# Peripherals.net
KiCad netlist of a schematic drawn in Altium Designer
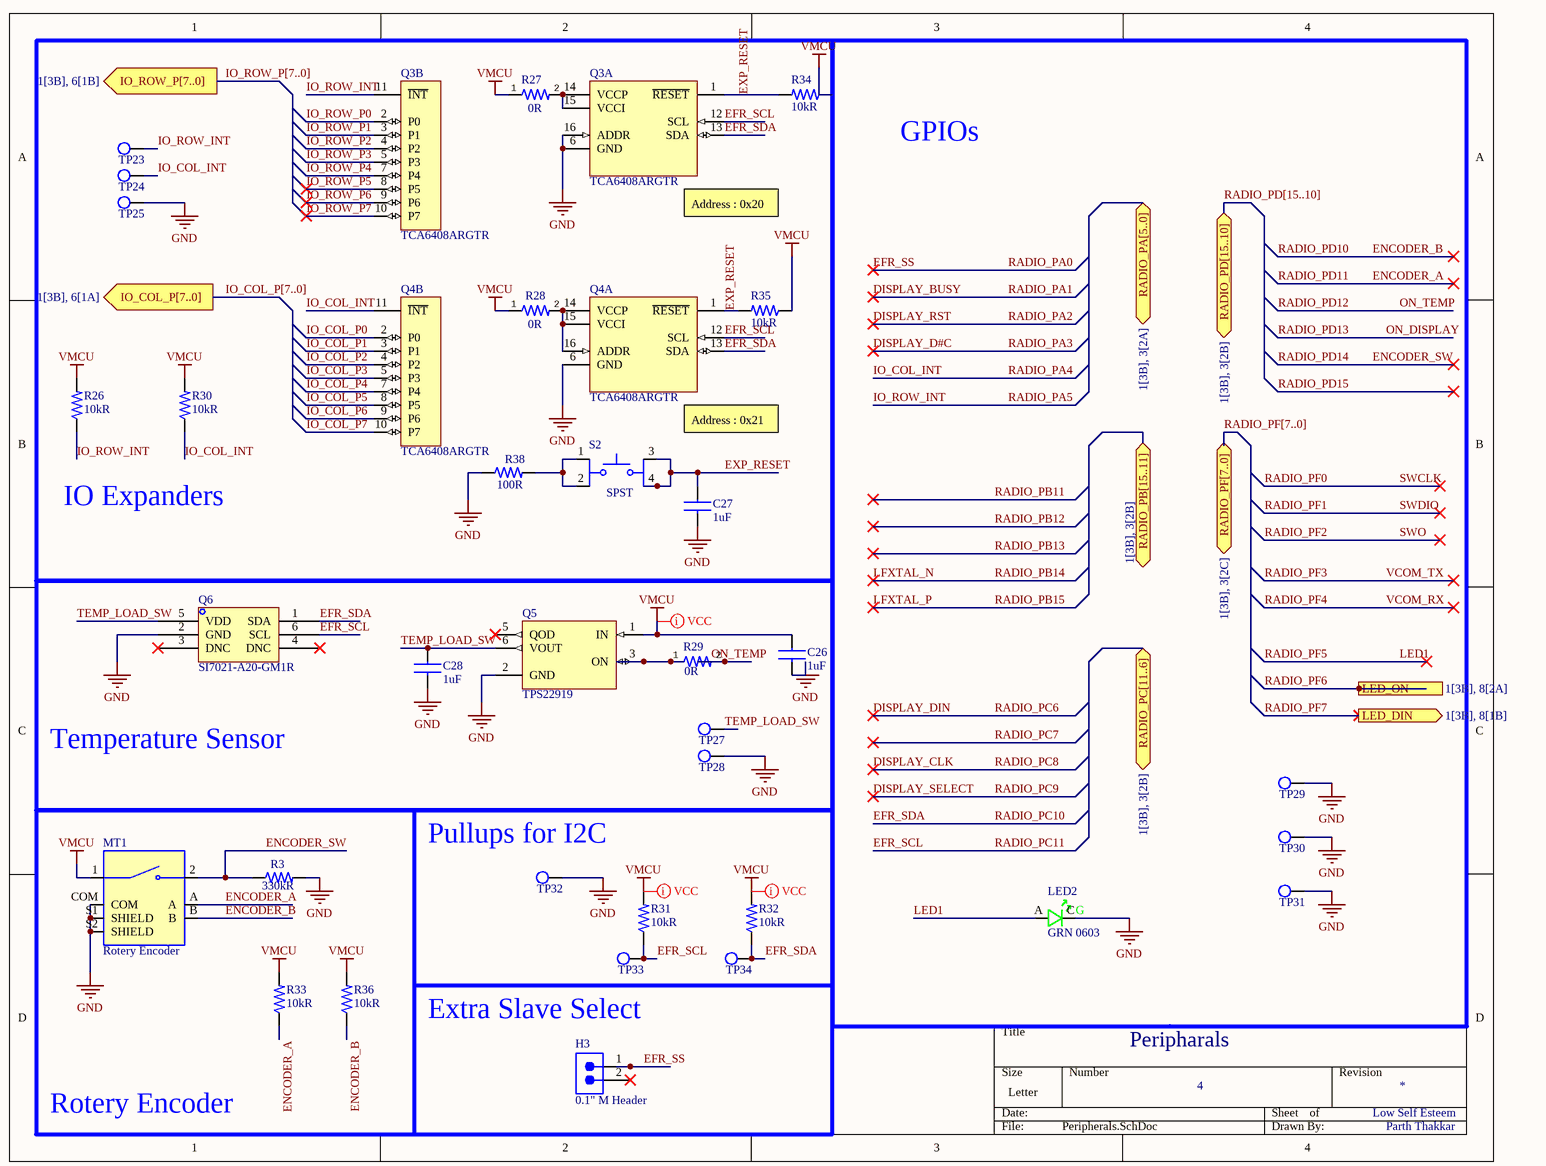
[diagram p0: Peripherals.SchDoc]

(export (version "E")
  (design (tool "Eeschema 10.0.6"))
  (components
    (comp (ref "C26")
      (value "1uF")
      (footprint "Capacitor 0603")
      (fields
        (field (name "MANUFACTURER") "Murata")
        (field (name "MANUFACTURER PART NUMBER") "GRM188R61A105KA61D")
        (field (name "Comment") "CAP 1uF 10V 0603")
      )
      (libsource (lib "Keyboard_parts") (part "CAP 1uF 10V 0603"))
    )
    (comp (ref "C27")
      (value "1uF")
      (footprint "Capacitor 0603")
      (fields
        (field (name "MANUFACTURER") "Murata")
        (field (name "MANUFACTURER PART NUMBER") "GRM188R61A105KA61D")
        (field (name "Comment") "CAP 1uF 10V 0603")
      )
      (libsource (lib "Keyboard_parts") (part "CAP 1uF 10V 0603"))
    )
    (comp (ref "C28")
      (value "1uF")
      (footprint "CAPACITOR 0805")
      (description "Multilayer Ceramic Capacitor, 1 uF, 10 V, ± 20%, X5R, 0201 [0603 Metric]")
      (fields
        (field (name "MANUFACTURER") "Murata")
        (field (name "MANUFACTURER PART NUMBER") "GRM033R61A105ME15D")
      )
      (libsource (lib "Keyboard_parts") (part "CAP 47uF 10V 0805"))
    )
    (comp (ref "H3")
      (value "0.1\" M Header")
      (footprint "2-PIN_MALE_HEADER_01-IN")
      (description "CONN HEADER VERT 2POS 2.54MM")
      (fields
        (field (name "MANUFACTURER") "Sullins")
        (field (name "MANUFACTURER PART NUMBER") "PRPC002SAAN-RC")
      )
      (libsource (lib "InsaneIntegratedLib") (part "PRPC002SAAN-RC"))
    )
    (comp (ref "LED2")
      (value "GRN 0603")
      (footprint "LED 0603")
      (description "LED, 0603, GREEN, 430MCD, 520NM")
      (fields
        (field (name "MANUFACTURER") "Wurth Electronics")
        (field (name "MANUFACTURER PART NUMBER") "150060GS75000")
      )
      (libsource (lib "InsaneIntegratedLib") (part "LED Green 0603"))
    )
    (comp (ref "MT1")
      (value "Rotery Encoder")
      (footprint "Rotery Encoder")
      (description "Rotary Position Encoder, Single, 2 Channels")
      (fields (field (name "MP") "PEC11R-4215F-S0024") (field (name "MANUFACTURER") "Bourns"))
      (libsource (lib "InsaneIntegratedLib") (part "Rotery Encoder"))
    )
    (comp (ref "Q3")
      (value "TCA6408ARGTR")
      (footprint "TCA6408ARGTR - IO Expander")
      (description "Parallel I/O Port, 8-Bit, 8 I/O, CMOS, PQCC16")
      (fields (field (name "MANUFACTURER") "Texas Instruments"))
      (libsource (lib "Keyboard_parts") (part "TCA6408ARGTR"))
    )
    (comp (ref "Q4")
      (value "TCA6408ARGTR")
      (footprint "TCA6408ARGTR - IO Expander")
      (description "Parallel I/O Port, 8-Bit, 8 I/O, CMOS, PQCC16")
      (fields (field (name "MANUFACTURER") "Texas Instruments"))
      (libsource (lib "Keyboard_parts") (part "TCA6408ARGTR"))
    )
    (comp (ref "Q5")
      (value "TPS22919")
      (footprint "TPS22919DCKR - Load SW")
      (description "Buffer/Inverter Based Peripheral Driver, 3A, PDSO6")
      (fields
        (field (name "MANUFACTURER") "Texas Instruments")
        (field (name "MANUFACTURER PART NUMBER") "TPS22919DCKT")
      )
      (libsource (lib "Keyboard_parts") (part "TPS22919"))
    )
    (comp (ref "Q6")
      (value "SI7021-A20-GM1R")
      (footprint "Si7021-A20 - Temp")
      (description "Serial Switch/Digital Sensor, 14 Bit(s), 0.40Cel, Square, Surface Mount")
      (fields (field (name "MANUFACTURER") "Silicon Labs"))
      (libsource (lib "Keyboard_parts") (part "SI7021-A20-GM1R"))
    )
    (comp (ref "R3")
      (value "330kR")
      (footprint "Resistor 0603")
      (fields
        (field (name "MANUFACTURER") "Yageo")
        (field (name "MANUFACTURER PART NUMBER") "RC0603JR-07330KL")
        (field (name "TOLERANCE") "5%")
      )
      (libsource (lib "Keyboard_parts") (part "RES 330K 0603"))
    )
    (comp (ref "R26")
      (value "10kR")
      (footprint "Resistor 0603")
      (fields
        (field (name "MANUFACTURER") "Yageo")
        (field (name "MANUFACTURER PART NUMBER") "RC0603FR-0710KL")
        (field (name "TOLERANCE") "1%")
      )
      (libsource (lib "Keyboard_parts") (part "RES 10K 0603"))
    )
    (comp (ref "R27")
      (value "0R")
      (footprint "Resistor 0402")
      (description "Metal Glaze/thick Film, 0.0625W, 0ohm, Surface Mount, 0402")
      (fields
        (field (name "MANUFACTURER") "Yageo")
        (field (name "MANUFACTURER PART NUMBER") "RC0402JR-070RL")
      )
      (libsource (lib "InsaneIntegratedLib") (part "RES 0R 0402"))
    )
    (comp (ref "R28")
      (value "0R")
      (footprint "Resistor 0402")
      (description "Metal Glaze/thick Film, 0.0625W, 0ohm, Surface Mount, 0402")
      (fields
        (field (name "MANUFACTURER") "Yageo")
        (field (name "MANUFACTURER PART NUMBER") "RC0402JR-070RL")
      )
      (libsource (lib "InsaneIntegratedLib") (part "RES 0R 0402"))
    )
    (comp (ref "R29")
      (value "0R")
      (footprint "Resistor 0402")
      (description "Metal Glaze/thick Film, 0.0625W, 0ohm, Surface Mount, 0402")
      (fields
        (field (name "MANUFACTURER") "Yageo")
        (field (name "MANUFACTURER PART NUMBER") "RC0402JR-070RL")
      )
      (libsource (lib "InsaneIntegratedLib") (part "RES 0R 0402"))
    )
    (comp (ref "R30")
      (value "10kR")
      (footprint "Resistor 0603")
      (fields
        (field (name "MANUFACTURER") "Yageo")
        (field (name "MANUFACTURER PART NUMBER") "RC0603FR-0710KL")
        (field (name "TOLERANCE") "1%")
      )
      (libsource (lib "Keyboard_parts") (part "RES 10K 0603"))
    )
    (comp (ref "R31")
      (value "10kR")
      (footprint "Resistor 0603")
      (fields
        (field (name "MANUFACTURER") "Yageo")
        (field (name "MANUFACTURER PART NUMBER") "RC0603FR-0710KL")
        (field (name "TOLERANCE") "1%")
      )
      (libsource (lib "Keyboard_parts") (part "RES 10K 0603"))
    )
    (comp (ref "R32")
      (value "10kR")
      (footprint "Resistor 0603")
      (fields
        (field (name "MANUFACTURER") "Yageo")
        (field (name "MANUFACTURER PART NUMBER") "RC0603FR-0710KL")
        (field (name "TOLERANCE") "1%")
      )
      (libsource (lib "Keyboard_parts") (part "RES 10K 0603"))
    )
    (comp (ref "R33")
      (value "10kR")
      (footprint "Resistor 0603")
      (fields
        (field (name "MANUFACTURER") "Yageo")
        (field (name "MANUFACTURER PART NUMBER") "RC0603FR-0710KL")
        (field (name "TOLERANCE") "1%")
      )
      (libsource (lib "Keyboard_parts") (part "RES 10K 0603"))
    )
    (comp (ref "R34")
      (value "10kR")
      (footprint "Resistor 0603")
      (fields
        (field (name "MANUFACTURER") "Yageo")
        (field (name "MANUFACTURER PART NUMBER") "RC0603FR-0710KL")
        (field (name "TOLERANCE") "1%")
      )
      (libsource (lib "Keyboard_parts") (part "RES 10K 0603"))
    )
    (comp (ref "R35")
      (value "10kR")
      (footprint "Resistor 0603")
      (fields
        (field (name "MANUFACTURER") "Yageo")
        (field (name "MANUFACTURER PART NUMBER") "RC0603FR-0710KL")
        (field (name "TOLERANCE") "1%")
      )
      (libsource (lib "Keyboard_parts") (part "RES 10K 0603"))
    )
    (comp (ref "R36")
      (value "10kR")
      (footprint "Resistor 0603")
      (fields
        (field (name "MANUFACTURER") "Yageo")
        (field (name "MANUFACTURER PART NUMBER") "RC0603FR-0710KL")
        (field (name "TOLERANCE") "1%")
      )
      (libsource (lib "Keyboard_parts") (part "RES 10K 0603"))
    )
    (comp (ref "R38")
      (value "100R")
      (footprint "Resistor 0603")
      (fields
        (field (name "MANUFACTURER") "Yageo")
        (field (name "MANUFACTURER PART NUMBER") "RC0603FR-07100RL")
        (field (name "TOLERANCE") "1%")
      )
      (libsource (lib "Keyboard_parts") (part "RES 100R 0603"))
    )
    (comp (ref "S2")
      (value "SPST")
      (footprint "SPST")
      (fields
        (field (name "MANUFACTURER") "E-Switch")
        (field (name "MANUFACTURER PART NUMBER") "TL3301NF260QG")
      )
      (libsource (lib "Keyboard_parts") (part "SPST"))
    )
    (comp (ref "TP23")
      (value "Test point")
      (footprint "Test Point")
      (libsource (lib "Keyboard_parts") (part "Test point"))
    )
    (comp (ref "TP24")
      (value "Test point")
      (footprint "Test Point")
      (libsource (lib "Keyboard_parts") (part "Test point"))
    )
    (comp (ref "TP25")
      (value "Test point")
      (footprint "Test Point")
      (libsource (lib "Keyboard_parts") (part "Test point"))
    )
    (comp (ref "TP27")
      (value "Test point")
      (footprint "Test Point")
      (libsource (lib "Keyboard_parts") (part "Test point"))
    )
    (comp (ref "TP28")
      (value "Test point")
      (footprint "Test Point")
      (libsource (lib "Keyboard_parts") (part "Test point"))
    )
    (comp (ref "TP29")
      (value "Test point")
      (footprint "Test Point")
      (libsource (lib "Keyboard_parts") (part "Test point"))
    )
    (comp (ref "TP30")
      (value "Test point")
      (footprint "Test Point")
      (libsource (lib "Keyboard_parts") (part "Test point"))
    )
    (comp (ref "TP31")
      (value "Test point")
      (footprint "Test Point")
      (libsource (lib "Keyboard_parts") (part "Test point"))
    )
    (comp (ref "TP32")
      (value "Test point")
      (footprint "Test Point")
      (libsource (lib "Keyboard_parts") (part "Test point"))
    )
    (comp (ref "TP33")
      (value "Test point")
      (footprint "Test Point")
      (libsource (lib "Keyboard_parts") (part "Test point"))
    )
    (comp (ref "TP34")
      (value "Test point")
      (footprint "Test Point")
      (libsource (lib "Keyboard_parts") (part "Test point"))
    )
  )
  (nets
    (net (code "1") (name "/EXP_RESET") (class "Default")
      (node (ref "C27") (pin "1") (pinfunction "1_1") (pintype "passive"))
      (node (ref "Q3") (pin "1") (pinfunction "~{RESET}_1") (pintype "passive"))
      (node (ref "Q4") (pin "1") (pinfunction "~{RESET}_1") (pintype "passive"))
      (node (ref "R34") (pin "2") (pinfunction "2_2") (pintype "passive"))
      (node (ref "R35") (pin "2") (pinfunction "2_2") (pintype "passive"))
      (node (ref "S2") (pin "3") (pinfunction "3_3") (pintype "passive"))
      (node (ref "S2") (pin "4") (pinfunction "4_4") (pintype "passive"))
    )
    (net (code "2") (name "/IO_COL_P0") (class "Default")
      (node (ref "Q4") (pin "2") (pinfunction "P0_2") (pintype "bidirectional"))
    )
    (net (code "3") (name "/IO_COL_P1") (class "Default")
      (node (ref "Q4") (pin "3") (pinfunction "P1_3") (pintype "bidirectional"))
    )
    (net (code "4") (name "/IO_COL_P2") (class "Default")
      (node (ref "Q4") (pin "4") (pinfunction "P2_4") (pintype "bidirectional"))
    )
    (net (code "5") (name "/IO_COL_P3") (class "Default")
      (node (ref "Q4") (pin "5") (pinfunction "P3_5") (pintype "bidirectional"))
    )
    (net (code "6") (name "/IO_COL_P4") (class "Default")
      (node (ref "Q4") (pin "7") (pinfunction "P4_7") (pintype "bidirectional"))
    )
    (net (code "7") (name "/IO_COL_P5") (class "Default")
      (node (ref "Q4") (pin "8") (pinfunction "P5_8") (pintype "bidirectional"))
    )
    (net (code "8") (name "/IO_COL_P6") (class "Default")
      (node (ref "Q4") (pin "9") (pinfunction "P6_9") (pintype "bidirectional"))
    )
    (net (code "9") (name "/IO_COL_P7") (class "Default")
      (node (ref "Q4") (pin "10") (pinfunction "P7_10") (pintype "bidirectional"))
    )
    (net (code "11") (name "/IO_ROW_P0") (class "Default")
      (node (ref "Q3") (pin "2") (pinfunction "P0_2") (pintype "bidirectional"))
    )
    (net (code "12") (name "/IO_ROW_P1") (class "Default")
      (node (ref "Q3") (pin "3") (pinfunction "P1_3") (pintype "bidirectional"))
    )
    (net (code "13") (name "/IO_ROW_P2") (class "Default")
      (node (ref "Q3") (pin "4") (pinfunction "P2_4") (pintype "bidirectional"))
    )
    (net (code "14") (name "/IO_ROW_P3") (class "Default")
      (node (ref "Q3") (pin "5") (pinfunction "P3_5") (pintype "bidirectional"))
    )
    (net (code "15") (name "/IO_ROW_P4") (class "Default")
      (node (ref "Q3") (pin "7") (pinfunction "P4_7") (pintype "bidirectional"))
    )
    (net (code "16") (name "/IO_ROW_P5") (class "Default")
      (node (ref "Q3") (pin "8") (pinfunction "P5_8") (pintype "bidirectional+no_connect"))
    )
    (net (code "17") (name "/IO_ROW_P6") (class "Default")
      (node (ref "Q3") (pin "9") (pinfunction "P6_9") (pintype "bidirectional+no_connect"))
    )
    (net (code "18") (name "/IO_ROW_P7") (class "Default")
      (node (ref "Q3") (pin "10") (pinfunction "P7_10") (pintype "bidirectional+no_connect"))
    )
    (net (code "20") (name "/RADIO_PA0") (class "Default")
      (node (ref "H3") (pin "1") (pinfunction "1_1") (pintype "passive"))
    )
    (net (code "24") (name "/RADIO_PA4") (class "Default")
      (node (ref "Q4") (pin "11") (pinfunction "~{INT}_11") (pintype "passive"))
      (node (ref "R30") (pin "1") (pinfunction "1_1") (pintype "passive"))
      (node (ref "TP24") (pin "1") (pinfunction "1_1") (pintype "passive"))
    )
    (net (code "25") (name "/RADIO_PA5") (class "Default")
      (node (ref "Q3") (pin "11") (pinfunction "~{INT}_11") (pintype "passive"))
      (node (ref "R26") (pin "1") (pinfunction "1_1") (pintype "passive"))
      (node (ref "TP23") (pin "1") (pinfunction "1_1") (pintype "passive"))
    )
    (net (code "37") (name "/RADIO_PC10") (class "Default")
      (node (ref "Q3") (pin "13") (pinfunction "SDA_13") (pintype "bidirectional"))
      (node (ref "Q4") (pin "13") (pinfunction "SDA_13") (pintype "bidirectional"))
      (node (ref "Q6") (pin "1") (pinfunction "SDA_1") (pintype "passive"))
      (node (ref "R32") (pin "1") (pinfunction "1_1") (pintype "passive"))
      (node (ref "TP34") (pin "1") (pinfunction "1_1") (pintype "passive"))
    )
    (net (code "38") (name "/RADIO_PC11") (class "Default")
      (node (ref "Q3") (pin "12") (pinfunction "SCL_12") (pintype "input"))
      (node (ref "Q4") (pin "12") (pinfunction "SCL_12") (pintype "input"))
      (node (ref "Q6") (pin "6") (pinfunction "SCL_6") (pintype "passive"))
      (node (ref "R31") (pin "1") (pinfunction "1_1") (pintype "passive"))
      (node (ref "TP33") (pin "1") (pinfunction "1_1") (pintype "passive"))
    )
    (net (code "40") (name "/RADIO_PD10") (class "Default")
      (node (ref "MT1") (pin "B") (pinfunction "B_B") (pintype "passive"))
      (node (ref "R36") (pin "1") (pinfunction "1_1") (pintype "passive"))
    )
    (net (code "41") (name "/RADIO_PD11") (class "Default")
      (node (ref "MT1") (pin "A") (pinfunction "A_A") (pintype "passive"))
      (node (ref "R33") (pin "1") (pinfunction "1_1") (pintype "passive"))
    )
    (net (code "42") (name "/RADIO_PD12") (class "Default")
      (node (ref "R29") (pin "2") (pinfunction "2_2") (pintype "passive"))
    )
    (net (code "44") (name "/RADIO_PD14") (class "Default")
      (node (ref "MT1") (pin "2") (pinfunction "2_2") (pintype "passive"))
      (node (ref "R3") (pin "1") (pinfunction "1_1") (pintype "passive"))
    )
    (net (code "52") (name "/RADIO_PF5") (class "Default")
      (node (ref "LED2") (pin "A") (pinfunction "A_A") (pintype "passive"))
    )
    (net (code "56") (name "/TEMP_LOAD_SW") (class "Default")
      (node (ref "C28") (pin "1") (pinfunction "1_1") (pintype "passive"))
      (node (ref "Q5") (pin "6") (pinfunction "VOUT_6") (pintype "output"))
      (node (ref "Q6") (pin "5") (pinfunction "VDD_5") (pintype "passive"))
      (node (ref "TP27") (pin "1") (pinfunction "1_1") (pintype "passive"))
    )
    (net (code "57") (name "GND") (class "Default")
      (node (ref "C26") (pin "2") (pinfunction "2_2") (pintype "passive"))
      (node (ref "C27") (pin "2") (pinfunction "2_2") (pintype "passive"))
      (node (ref "C28") (pin "2") (pinfunction "2_2") (pintype "passive"))
      (node (ref "LED2") (pin "C") (pinfunction "C_C") (pintype "passive"))
      (node (ref "MT1") (pin "COM") (pinfunction "COM_COM") (pintype "passive"))
      (node (ref "MT1") (pin "S1") (pinfunction "SHIELD_S1") (pintype "passive"))
      (node (ref "MT1") (pin "S2") (pinfunction "SHIELD_S2") (pintype "passive"))
      (node (ref "Q3") (pin "16") (pinfunction "ADDR_16") (pintype "input"))
      (node (ref "Q3") (pin "6") (pinfunction "GND_6") (pintype "passive"))
      (node (ref "Q4") (pin "6") (pinfunction "GND_6") (pintype "passive"))
      (node (ref "Q5") (pin "2") (pinfunction "GND_2") (pintype "power_in"))
      (node (ref "Q6") (pin "2") (pinfunction "GND_2") (pintype "passive"))
      (node (ref "R3") (pin "2") (pinfunction "2_2") (pintype "passive"))
      (node (ref "R38") (pin "1") (pinfunction "1_1") (pintype "passive"))
      (node (ref "TP25") (pin "1") (pinfunction "1_1") (pintype "passive"))
      (node (ref "TP28") (pin "1") (pinfunction "1_1") (pintype "passive"))
      (node (ref "TP29") (pin "1") (pinfunction "1_1") (pintype "passive"))
      (node (ref "TP30") (pin "1") (pinfunction "1_1") (pintype "passive"))
      (node (ref "TP31") (pin "1") (pinfunction "1_1") (pintype "passive"))
      (node (ref "TP32") (pin "1") (pinfunction "1_1") (pintype "passive"))
    )
    (net (code "58") (name "Net-(Q3A-VCCI)") (class "Default")
      (node (ref "Q3") (pin "14") (pinfunction "VCCP_14") (pintype "power_in"))
      (node (ref "Q3") (pin "15") (pinfunction "VCCI_15") (pintype "power_in"))
      (node (ref "R27") (pin "2") (pinfunction "2_2") (pintype "passive"))
    )
    (net (code "59") (name "Net-(Q4A-ADDR)") (class "Default")
      (node (ref "Q4") (pin "14") (pinfunction "VCCP_14") (pintype "power_in"))
      (node (ref "Q4") (pin "15") (pinfunction "VCCI_15") (pintype "power_in"))
      (node (ref "Q4") (pin "16") (pinfunction "ADDR_16") (pintype "input"))
      (node (ref "R28") (pin "2") (pinfunction "2_2") (pintype "passive"))
    )
    (net (code "60") (name "Net-(Q5-ON)") (class "Default")
      (node (ref "Q5") (pin "3") (pinfunction "ON_3") (pintype "bidirectional"))
      (node (ref "R29") (pin "1") (pinfunction "1_1") (pintype "passive"))
    )
    (net (code "61") (name "Net-(R38-Pad2)") (class "Default")
      (node (ref "R38") (pin "2") (pinfunction "2_2") (pintype "passive"))
      (node (ref "S2") (pin "1") (pinfunction "1_1") (pintype "passive"))
      (node (ref "S2") (pin "2") (pinfunction "2_2") (pintype "passive"))
    )
    (net (code "62") (name "VMCU") (class "Default")
      (node (ref "C26") (pin "1") (pinfunction "1_1") (pintype "passive"))
      (node (ref "MT1") (pin "1") (pinfunction "1_1") (pintype "passive"))
      (node (ref "Q5") (pin "1") (pinfunction "IN_1") (pintype "input"))
      (node (ref "R26") (pin "2") (pinfunction "2_2") (pintype "passive"))
      (node (ref "R27") (pin "1") (pinfunction "1_1") (pintype "passive"))
      (node (ref "R28") (pin "1") (pinfunction "1_1") (pintype "passive"))
      (node (ref "R30") (pin "2") (pinfunction "2_2") (pintype "passive"))
      (node (ref "R31") (pin "2") (pinfunction "2_2") (pintype "passive"))
      (node (ref "R32") (pin "2") (pinfunction "2_2") (pintype "passive"))
      (node (ref "R33") (pin "2") (pinfunction "2_2") (pintype "passive"))
      (node (ref "R34") (pin "1") (pinfunction "1_1") (pintype "passive"))
      (node (ref "R35") (pin "1") (pinfunction "1_1") (pintype "passive"))
      (node (ref "R36") (pin "2") (pinfunction "2_2") (pintype "passive"))
    )
    (net (code "63") (name "unconnected-(H3-Pad2)") (class "Default")
      (node (ref "H3") (pin "2") (pinfunction "2_2") (pintype "passive+no_connect"))
    )
    (net (code "64") (name "unconnected-(Q5-QOD-Pad5)") (class "Default")
      (node (ref "Q5") (pin "5") (pinfunction "QOD_5") (pintype "output+no_connect"))
    )
    (net (code "65") (name "unconnected-(Q6-DNC-Pad3)") (class "Default")
      (node (ref "Q6") (pin "3") (pinfunction "DNC_3") (pintype "passive+no_connect"))
    )
    (net (code "66") (name "unconnected-(Q6-DNC-Pad4)") (class "Default")
      (node (ref "Q6") (pin "4") (pinfunction "DNC_4") (pintype "passive+no_connect"))
    )
  )
)
